# PRO3.net
KiCad netlist of a schematic drawn in Altium Designer
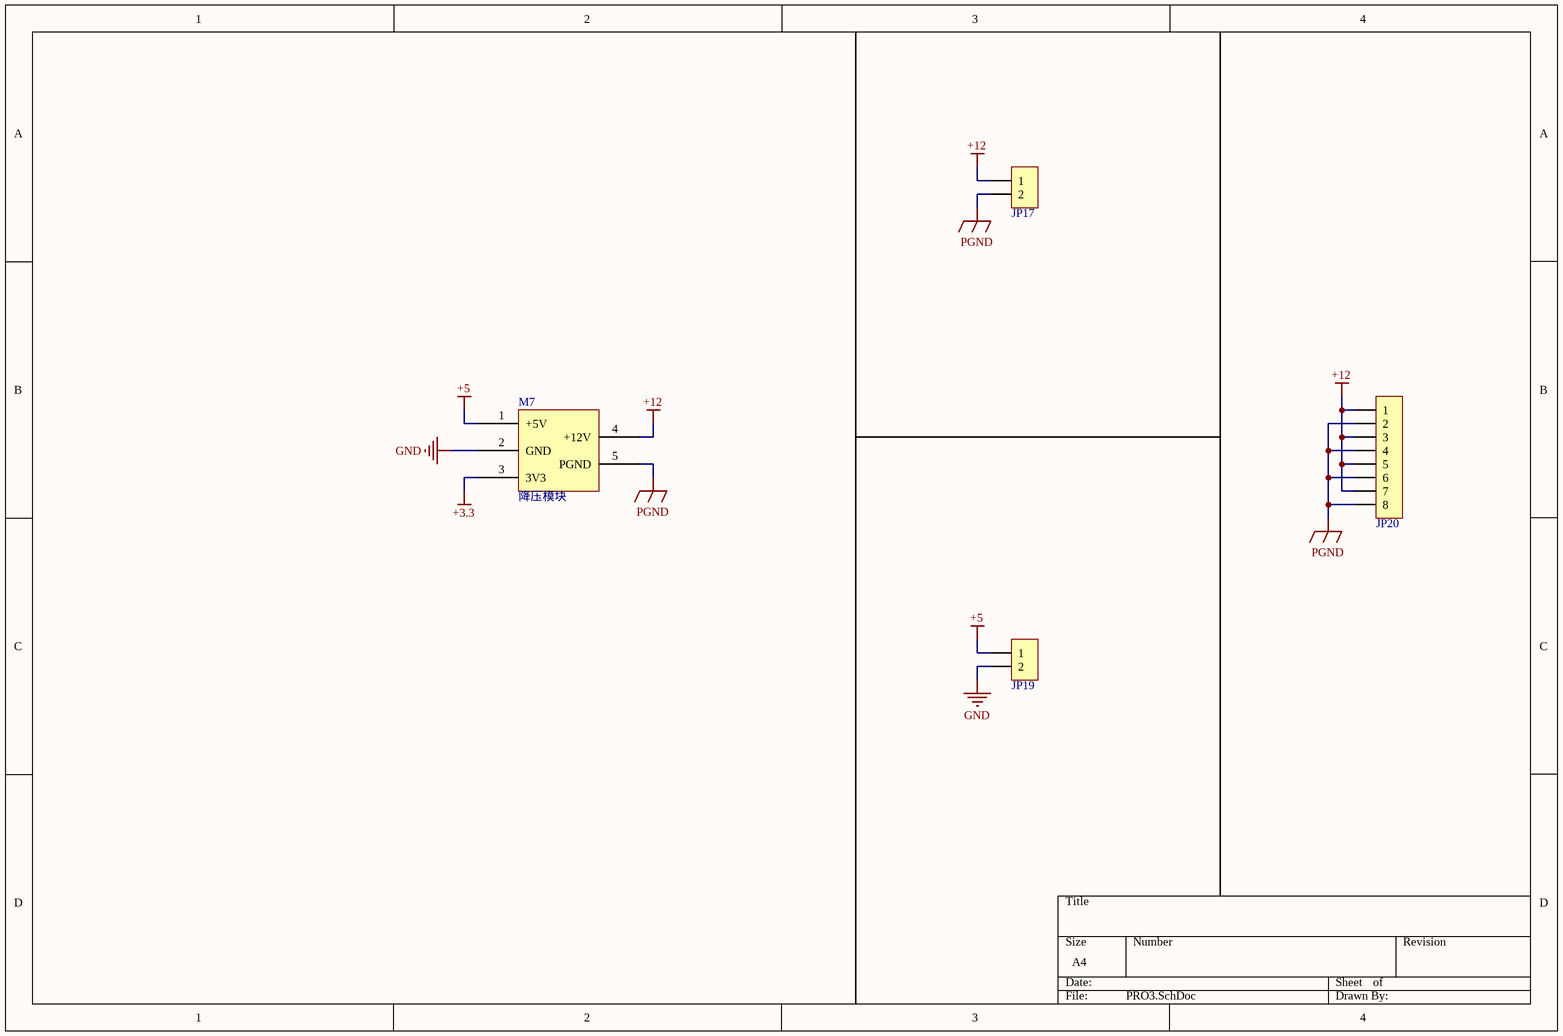
[diagram p0: PRO3.SchDoc]

(export (version "E")
  (design (tool "Eeschema 10.0.6"))
  (components
    (comp (ref "JP17")
      (value "HDR-1X2")
      (footprint "KF128-5.08-2P")
      (description "2P接插件")
      (fields (field (name "版权归属") "源创客"))
      (libsource (lib "4.10 - 接插件-脚距5.08") (part "Header 2"))
    )
    (comp (ref "JP19")
      (value "HDR-1X2")
      (footprint "KF128-5.08-2P")
      (description "2P接插件")
      (fields (field (name "版权归属") "源创客"))
      (libsource (lib "4.10 - 接插件-脚距5.08") (part "Header 2"))
    )
    (comp (ref "JP20")
      (value "HDR-1X8")
      (footprint "KF128-5.08-8P")
      (description "8P接插件")
      (fields (field (name "版权归属") "源创客"))
      (libsource (lib "4.10 - 接插件-脚距5.08") (part "Header 8"))
    )
    (comp (ref "M7") (value "降压模块") (footprint "一号电压板") (libsource (lib "power") (part "一号电压板")))
  )
  (nets
    (net (code "1") (name "+3.3") (class "Default")
      (node (ref "M7") (pin "3") (pinfunction "3V3_3") (pintype "passive"))
    )
    (net (code "2") (name "+5") (class "Default")
      (node (ref "JP19") (pin "1") (pinfunction "1_1") (pintype "passive"))
      (node (ref "M7") (pin "1") (pinfunction "+5V_1") (pintype "passive"))
    )
    (net (code "3") (name "+12") (class "Default")
      (node (ref "JP17") (pin "1") (pinfunction "1_1") (pintype "passive"))
      (node (ref "JP20") (pin "1") (pinfunction "1_1") (pintype "passive"))
      (node (ref "JP20") (pin "3") (pinfunction "3_3") (pintype "passive"))
      (node (ref "JP20") (pin "5") (pinfunction "5_5") (pintype "passive"))
      (node (ref "JP20") (pin "7") (pinfunction "7_7") (pintype "passive"))
      (node (ref "M7") (pin "4") (pinfunction "+12V_4") (pintype "passive"))
    )
    (net (code "4") (name "GND") (class "Default")
      (node (ref "JP19") (pin "2") (pinfunction "2_2") (pintype "passive"))
      (node (ref "M7") (pin "2") (pinfunction "GND_2") (pintype "passive"))
    )
    (net (code "5") (name "PGND") (class "Default")
      (node (ref "JP17") (pin "2") (pinfunction "2_2") (pintype "passive"))
      (node (ref "JP20") (pin "2") (pinfunction "2_2") (pintype "passive"))
      (node (ref "JP20") (pin "4") (pinfunction "4_4") (pintype "passive"))
      (node (ref "JP20") (pin "6") (pinfunction "6_6") (pintype "passive"))
      (node (ref "JP20") (pin "8") (pinfunction "8_8") (pintype "passive"))
      (node (ref "M7") (pin "5") (pinfunction "PGND_5") (pintype "passive"))
    )
  )
)
